# 8pin-CC1101-Adapter.net
KiCad netlist of a schematic drawn in EAGLE
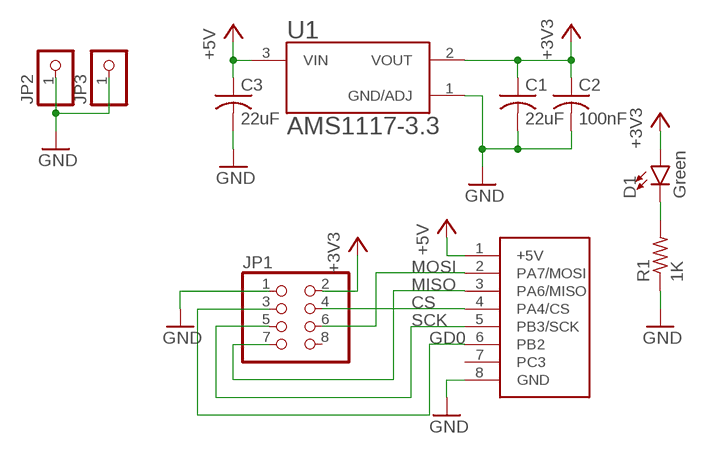
[diagram p0: schematic, sheet 1]

(export (version "E")
  (design (tool "Eeschema 10.0.6"))
  (components
    (comp (ref "C1")
      (value "22uF")
      (footprint "eagle-import:C3216")
      (libsource (lib "eagle-import") (part "C-USC3216"))
    )
    (comp (ref "C2")
      (value "100nF")
      (footprint "eagle-import:C0805")
      (libsource (lib "eagle-import") (part "C-USC0805"))
    )
    (comp (ref "C3")
      (value "22uF")
      (footprint "eagle-import:C3216")
      (libsource (lib "eagle-import") (part "C-USC3216"))
    )
    (comp (ref "D1")
      (value "Green")
      (footprint "eagle-import:LED-0603")
      (libsource (lib "eagle-import") (part "LED-GREEN0603"))
    )
    (comp (ref "JP1")
      (value "PINHD-2X4")
      (footprint "eagle-import:2X04")
      (libsource (lib "eagle-import") (part "PINHD-2X4"))
    )
    (comp (ref "JP2")
      (value "PINHD-1X1")
      (footprint "eagle-import:1X01")
      (libsource (lib "eagle-import") (part "PINHD-1X1"))
    )
    (comp (ref "JP3")
      (value "PINHD-1X1")
      (footprint "eagle-import:1X01")
      (libsource (lib "eagle-import") (part "PINHD-1X1"))
    )
    (comp (ref "R1")
      (value "1K")
      (footprint "eagle-import:R0603")
      (libsource (lib "eagle-import") (part "R-US_R0603"))
    )
    (comp (ref "U$1")
      (value "LEFT-H1-SMD")
      (footprint "eagle-import:LEFT-H1-SMD")
      (libsource (lib "eagle-import") (part "LEFT-H1-SMD"))
    )
    (comp (ref "U1")
      (value "AMS1117-3.3")
      (footprint "eagle-import:SOT229P700X180-4N")
      (fields (field (name "MF") "Advanced Monolithic Systems"))
      (libsource (lib "eagle-import") (part "AMS1117-3.3"))
    )
  )
  (nets
    (net (code "1") (name "+3V3") (class "Default")
      (node (ref "C1") (pin "1") (pinfunction "1_1") (pintype "passive"))
      (node (ref "C2") (pin "1") (pinfunction "1_1") (pintype "passive"))
      (node (ref "D1") (pin "A") (pinfunction "A_A") (pintype "passive"))
      (node (ref "JP1") (pin "2") (pinfunction "2_2") (pintype "passive"))
      (node (ref "U1") (pin "2") (pinfunction "VOUT_2") (pintype "output"))
    )
    (net (code "2") (name "+5V") (class "Default")
      (node (ref "C3") (pin "1") (pinfunction "1_1") (pintype "passive"))
      (node (ref "U$1") (pin "1") (pinfunction "+5V_1") (pintype "bidirectional"))
      (node (ref "U1") (pin "3") (pinfunction "VIN_3") (pintype "input"))
    )
    (net (code "3") (name "/CS") (class "Default")
      (node (ref "JP1") (pin "4") (pinfunction "4_4") (pintype "passive"))
      (node (ref "U$1") (pin "4") (pinfunction "PA4/CS_4") (pintype "bidirectional"))
    )
    (net (code "4") (name "/GD0") (class "Default")
      (node (ref "JP1") (pin "3") (pinfunction "3_3") (pintype "passive"))
      (node (ref "U$1") (pin "6") (pinfunction "PB2_6") (pintype "bidirectional"))
    )
    (net (code "5") (name "/MISO") (class "Default")
      (node (ref "JP1") (pin "7") (pinfunction "7_7") (pintype "passive"))
      (node (ref "U$1") (pin "3") (pinfunction "PA6/MISO_3") (pintype "bidirectional"))
    )
    (net (code "6") (name "/MOSI") (class "Default")
      (node (ref "JP1") (pin "6") (pinfunction "6_6") (pintype "passive"))
      (node (ref "U$1") (pin "2") (pinfunction "PA7/MOSI_2") (pintype "bidirectional"))
    )
    (net (code "7") (name "/SCK") (class "Default")
      (node (ref "JP1") (pin "5") (pinfunction "5_5") (pintype "passive"))
      (node (ref "U$1") (pin "5") (pinfunction "PB3/SCK_5") (pintype "bidirectional"))
    )
    (net (code "8") (name "GND") (class "Default")
      (node (ref "C1") (pin "2") (pinfunction "2_2") (pintype "passive"))
      (node (ref "C2") (pin "2") (pinfunction "2_2") (pintype "passive"))
      (node (ref "C3") (pin "2") (pinfunction "2_2") (pintype "passive"))
      (node (ref "JP1") (pin "1") (pinfunction "1_1") (pintype "passive"))
      (node (ref "JP2") (pin "1") (pinfunction "1_1") (pintype "passive"))
      (node (ref "JP3") (pin "1") (pinfunction "1_1") (pintype "passive"))
      (node (ref "R1") (pin "1") (pinfunction "1_1") (pintype "passive"))
      (node (ref "U$1") (pin "8") (pinfunction "GND_8") (pintype "bidirectional"))
      (node (ref "U1") (pin "1") (pinfunction "GND/ADJ_1") (pintype "power_in"))
    )
    (net (code "9") (name "Net-(D1-PadC)") (class "Default")
      (node (ref "D1") (pin "C") (pinfunction "C_C") (pintype "passive"))
      (node (ref "R1") (pin "2") (pinfunction "2_2") (pintype "passive"))
    )
    (net (code "10") (name "unconnected-(JP1-Pad8)") (class "Default")
      (node (ref "JP1") (pin "8") (pinfunction "8_8") (pintype "passive"))
    )
    (net (code "11") (name "unconnected-(U$1-PC3-Pad7)") (class "Default")
      (node (ref "U$1") (pin "7") (pinfunction "PC3_7") (pintype "bidirectional"))
    )
  )
)
